# BatManagement.net
KiCad netlist of a schematic drawn in EAGLE
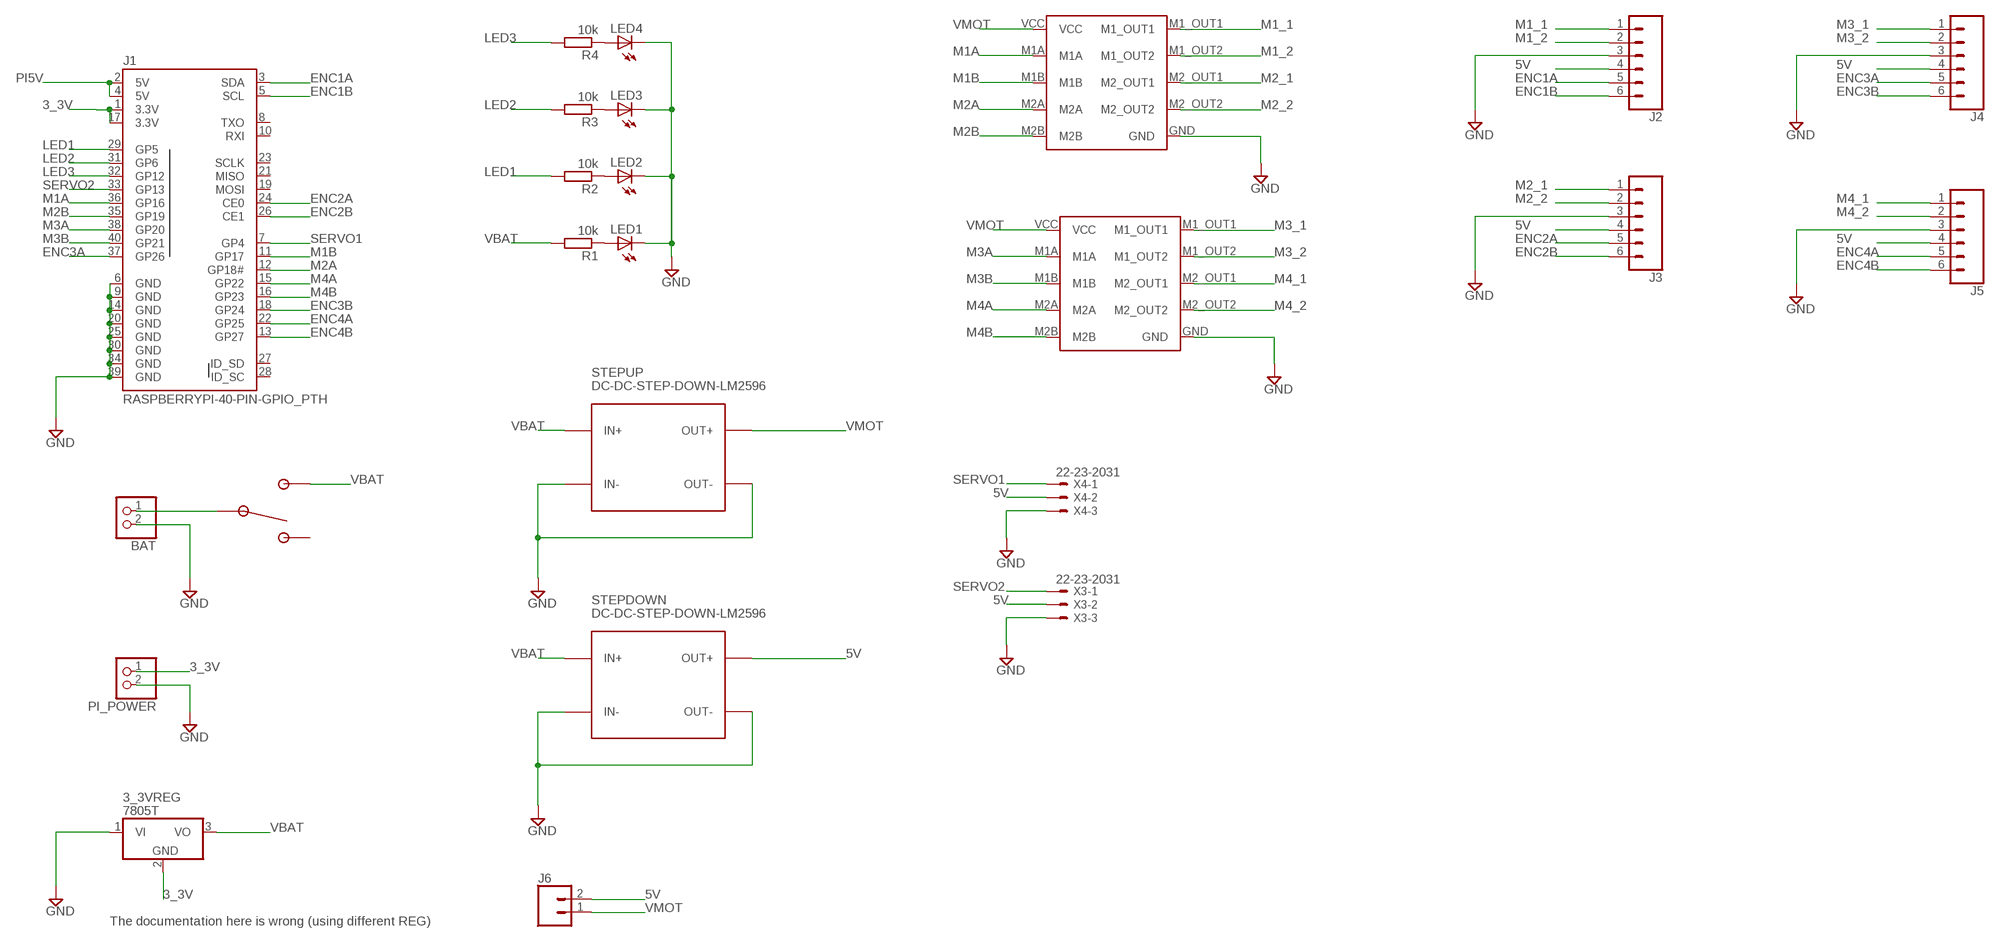
[diagram p0: schematic, sheet 1]

(export (version "E")
  (design (tool "Eeschema 10.0.6"))
  (components
    (comp (ref "3_3VREG")
      (value "7805T")
      (footprint "eagle-import:TO220H")
      (libsource (lib "eagle-import") (part "78T05"))
    )
    (comp (ref "BAT")
      (value "JST_2PIN-THM")
      (footprint "eagle-import:JST-PH-2-THM")
      (libsource (lib "eagle-import") (part "JST_2PIN-THM"))
    )
    (comp (ref "J1")
      (value "RASPBERRYPI-40-PIN-GPIO_PTH")
      (footprint "eagle-import:2X20_SHROUDED")
      (libsource (lib "eagle-import") (part "RASPBERRYPI-40-PIN-GPIO_PTH"))
    )
    (comp (ref "J2")
      (value "CONN_06SILK_FEMALE_PTH")
      (footprint "eagle-import:1X06")
      (libsource (lib "eagle-import") (part "CONN_06SILK_FEMALE_PTH"))
    )
    (comp (ref "J3")
      (value "CONN_06SILK_FEMALE_PTH")
      (footprint "eagle-import:1X06")
      (libsource (lib "eagle-import") (part "CONN_06SILK_FEMALE_PTH"))
    )
    (comp (ref "J4")
      (value "CONN_06SILK_FEMALE_PTH")
      (footprint "eagle-import:1X06")
      (libsource (lib "eagle-import") (part "CONN_06SILK_FEMALE_PTH"))
    )
    (comp (ref "J5")
      (value "CONN_06SILK_FEMALE_PTH")
      (footprint "eagle-import:1X06")
      (libsource (lib "eagle-import") (part "CONN_06SILK_FEMALE_PTH"))
    )
    (comp (ref "J6")
      (value "CONN_02")
      (footprint "eagle-import:1X02")
      (libsource (lib "eagle-import") (part "CONN_02"))
    )
    (comp (ref "LED1")
      (value "LED5MM")
      (footprint "eagle-import:LED5MM")
      (libsource (lib "eagle-import") (part "LED5MM"))
    )
    (comp (ref "LED2")
      (value "LED5MM")
      (footprint "eagle-import:LED5MM")
      (libsource (lib "eagle-import") (part "LED5MM"))
    )
    (comp (ref "LED3")
      (value "LED5MM")
      (footprint "eagle-import:LED5MM")
      (libsource (lib "eagle-import") (part "LED5MM"))
    )
    (comp (ref "LED4")
      (value "LED5MM")
      (footprint "eagle-import:LED5MM")
      (libsource (lib "eagle-import") (part "LED5MM"))
    )
    (comp (ref "MDRIVER1")
      (value "LV8548MC_BOARD")
      (footprint "eagle-import:LV8548MC_BOARD")
      (libsource (lib "eagle-import") (part "LV8548MC_BOARD"))
    )
    (comp (ref "MDRIVER2")
      (value "LV8548MC_BOARD")
      (footprint "eagle-import:LV8548MC_BOARD")
      (libsource (lib "eagle-import") (part "LV8548MC_BOARD"))
    )
    (comp (ref "PI_POWER")
      (value "JST_2PIN-THM")
      (footprint "eagle-import:JST-PH-2-THM")
      (libsource (lib "eagle-import") (part "JST_2PIN-THM"))
    )
    (comp (ref "R1")
      (value "10k")
      (footprint "eagle-import:0204_5")
      (libsource (lib "eagle-import") (part "R-EU_0204/5"))
    )
    (comp (ref "R2")
      (value "10k")
      (footprint "eagle-import:0204_5")
      (libsource (lib "eagle-import") (part "R-EU_0204/5"))
    )
    (comp (ref "R3")
      (value "10k")
      (footprint "eagle-import:0204_5")
      (libsource (lib "eagle-import") (part "R-EU_0204/5"))
    )
    (comp (ref "R4")
      (value "10k")
      (footprint "eagle-import:0204_5")
      (libsource (lib "eagle-import") (part "R-EU_0204/5"))
    )
    (comp (ref "STEPDOWN")
      (value "DC-DC-STEP-DOWN-LM2596")
      (footprint "eagle-import:DC-DC-STEP-DOWN-LM2596")
      (libsource (lib "eagle-import") (part "DC-DC-STEP-DOWN-LM2596"))
    )
    (comp (ref "STEPUP")
      (value "DC-DC-STEP-DOWN-LM2596")
      (footprint "eagle-import:DC-DC-STEP-DOWN-LM2596")
      (libsource (lib "eagle-import") (part "DC-DC-STEP-DOWN-LM2596"))
    )
    (comp (ref "SW1")
      (value "100SP1T2B4M6QE")
      (footprint "eagle-import:TOGGLE_RA")
      (fields (field (name "MF") "E-Switch"))
      (libsource (lib "eagle-import") (part "100SP1T2B4M6QE"))
    )
    (comp (ref "X3")
      (value "22-23-2031")
      (footprint "eagle-import:22-23-2031")
      (fields (field (name "MF") "MOLEX"))
      (libsource (lib "eagle-import") (part "22-23-2031"))
    )
    (comp (ref "X4")
      (value "22-23-2031")
      (footprint "eagle-import:22-23-2031")
      (fields (field (name "MF") "MOLEX"))
      (libsource (lib "eagle-import") (part "22-23-2031"))
    )
  )
  (nets
    (net (code "1") (name "/3_3V") (class "Default")
      (node (ref "3_3VREG") (pin "2") (pinfunction "GND_2") (pintype "passive"))
      (node (ref "J1") (pin "1") (pinfunction "3.3V_1") (pintype "power_in"))
      (node (ref "J1") (pin "17") (pinfunction "3.3V_17") (pintype "power_in"))
      (node (ref "PI_POWER") (pin "1") (pinfunction "2_1") (pintype "passive"))
    )
    (net (code "2") (name "/5V") (class "Default")
      (node (ref "J2") (pin "4") (pinfunction "4_4") (pintype "passive"))
      (node (ref "J3") (pin "4") (pinfunction "4_4") (pintype "passive"))
      (node (ref "J4") (pin "4") (pinfunction "4_4") (pintype "passive"))
      (node (ref "J5") (pin "4") (pinfunction "4_4") (pintype "passive"))
      (node (ref "J6") (pin "2") (pinfunction "2_2") (pintype "passive"))
      (node (ref "STEPDOWN") (pin "OUT+") (pinfunction "OUT+_OUT+") (pintype "bidirectional"))
      (node (ref "X3") (pin "2") (pinfunction "S_2") (pintype "passive"))
      (node (ref "X4") (pin "2") (pinfunction "S_2") (pintype "passive"))
    )
    (net (code "3") (name "/ENC1A") (class "Default")
      (node (ref "J1") (pin "3") (pinfunction "SDA_3") (pintype "bidirectional"))
      (node (ref "J2") (pin "5") (pinfunction "5_5") (pintype "passive"))
    )
    (net (code "4") (name "/ENC1B") (class "Default")
      (node (ref "J1") (pin "5") (pinfunction "SCL_5") (pintype "bidirectional"))
      (node (ref "J2") (pin "6") (pinfunction "6_6") (pintype "passive"))
    )
    (net (code "5") (name "/ENC2A") (class "Default")
      (node (ref "J1") (pin "24") (pinfunction "CE0_24") (pintype "output"))
      (node (ref "J3") (pin "5") (pinfunction "5_5") (pintype "passive"))
    )
    (net (code "6") (name "/ENC2B") (class "Default")
      (node (ref "J1") (pin "26") (pinfunction "CE1_26") (pintype "output"))
      (node (ref "J3") (pin "6") (pinfunction "6_6") (pintype "passive"))
    )
    (net (code "7") (name "/ENC3A") (class "Default")
      (node (ref "J1") (pin "37") (pinfunction "GP26_37") (pintype "bidirectional"))
      (node (ref "J4") (pin "5") (pinfunction "5_5") (pintype "passive"))
    )
    (net (code "8") (name "/ENC3B") (class "Default")
      (node (ref "J1") (pin "18") (pinfunction "GP24_18") (pintype "bidirectional"))
      (node (ref "J4") (pin "6") (pinfunction "6_6") (pintype "passive"))
    )
    (net (code "9") (name "/ENC4A") (class "Default")
      (node (ref "J1") (pin "22") (pinfunction "GP25_22") (pintype "bidirectional"))
      (node (ref "J5") (pin "5") (pinfunction "5_5") (pintype "passive"))
    )
    (net (code "10") (name "/ENC4B") (class "Default")
      (node (ref "J1") (pin "13") (pinfunction "GP27_13") (pintype "bidirectional"))
      (node (ref "J5") (pin "6") (pinfunction "6_6") (pintype "passive"))
    )
    (net (code "11") (name "/LED1") (class "Default")
      (node (ref "J1") (pin "29") (pinfunction "GP5_29") (pintype "bidirectional"))
      (node (ref "R2") (pin "2") (pinfunction "2_2") (pintype "passive"))
    )
    (net (code "12") (name "/LED2") (class "Default")
      (node (ref "J1") (pin "31") (pinfunction "GP6_31") (pintype "bidirectional"))
      (node (ref "R3") (pin "2") (pinfunction "2_2") (pintype "passive"))
    )
    (net (code "13") (name "/LED3") (class "Default")
      (node (ref "J1") (pin "32") (pinfunction "GP12_32") (pintype "bidirectional"))
      (node (ref "R4") (pin "2") (pinfunction "2_2") (pintype "passive"))
    )
    (net (code "14") (name "/M1A") (class "Default")
      (node (ref "J1") (pin "36") (pinfunction "GP16_36") (pintype "bidirectional"))
      (node (ref "MDRIVER1") (pin "M1A") (pinfunction "M1A_M1A") (pintype "bidirectional"))
    )
    (net (code "15") (name "/M1B") (class "Default")
      (node (ref "J1") (pin "11") (pinfunction "GP17_11") (pintype "bidirectional"))
      (node (ref "MDRIVER1") (pin "M1B") (pinfunction "M1B_M1B") (pintype "bidirectional"))
    )
    (net (code "16") (name "/M1_1") (class "Default")
      (node (ref "J2") (pin "1") (pinfunction "1_1") (pintype "passive"))
      (node (ref "MDRIVER1") (pin "M1_OUT1") (pinfunction "M1_OUT1_M1_OUT1") (pintype "bidirectional"))
    )
    (net (code "17") (name "/M1_2") (class "Default")
      (node (ref "J2") (pin "2") (pinfunction "2_2") (pintype "passive"))
      (node (ref "MDRIVER1") (pin "M1_OUT2") (pinfunction "M1_OUT2_M1_OUT2") (pintype "bidirectional"))
    )
    (net (code "18") (name "/M2A") (class "Default")
      (node (ref "J1") (pin "12") (pinfunction "GP18#_12") (pintype "bidirectional"))
      (node (ref "MDRIVER1") (pin "M2A") (pinfunction "M2A_M2A") (pintype "bidirectional"))
    )
    (net (code "19") (name "/M2B") (class "Default")
      (node (ref "J1") (pin "35") (pinfunction "GP19_35") (pintype "bidirectional"))
      (node (ref "MDRIVER1") (pin "M2B") (pinfunction "M2B_M2B") (pintype "bidirectional"))
    )
    (net (code "20") (name "/M2_1") (class "Default")
      (node (ref "J3") (pin "1") (pinfunction "1_1") (pintype "passive"))
      (node (ref "MDRIVER1") (pin "M2_OUT1") (pinfunction "M2_OUT1_M2_OUT1") (pintype "bidirectional"))
    )
    (net (code "21") (name "/M2_2") (class "Default")
      (node (ref "J3") (pin "2") (pinfunction "2_2") (pintype "passive"))
      (node (ref "MDRIVER1") (pin "M2_OUT2") (pinfunction "M2_OUT2_M2_OUT2") (pintype "bidirectional"))
    )
    (net (code "22") (name "/M3A") (class "Default")
      (node (ref "J1") (pin "38") (pinfunction "GP20_38") (pintype "bidirectional"))
      (node (ref "MDRIVER2") (pin "M1A") (pinfunction "M1A_M1A") (pintype "bidirectional"))
    )
    (net (code "23") (name "/M3B") (class "Default")
      (node (ref "J1") (pin "40") (pinfunction "GP21_40") (pintype "bidirectional"))
      (node (ref "MDRIVER2") (pin "M1B") (pinfunction "M1B_M1B") (pintype "bidirectional"))
    )
    (net (code "24") (name "/M3_1") (class "Default")
      (node (ref "J4") (pin "1") (pinfunction "1_1") (pintype "passive"))
      (node (ref "MDRIVER2") (pin "M1_OUT1") (pinfunction "M1_OUT1_M1_OUT1") (pintype "bidirectional"))
    )
    (net (code "25") (name "/M3_2") (class "Default")
      (node (ref "J4") (pin "2") (pinfunction "2_2") (pintype "passive"))
      (node (ref "MDRIVER2") (pin "M1_OUT2") (pinfunction "M1_OUT2_M1_OUT2") (pintype "bidirectional"))
    )
    (net (code "26") (name "/M4A") (class "Default")
      (node (ref "J1") (pin "15") (pinfunction "GP22_15") (pintype "bidirectional"))
      (node (ref "MDRIVER2") (pin "M2A") (pinfunction "M2A_M2A") (pintype "bidirectional"))
    )
    (net (code "27") (name "/M4B") (class "Default")
      (node (ref "J1") (pin "16") (pinfunction "GP23_16") (pintype "bidirectional"))
      (node (ref "MDRIVER2") (pin "M2B") (pinfunction "M2B_M2B") (pintype "bidirectional"))
    )
    (net (code "28") (name "/M4_1") (class "Default")
      (node (ref "J5") (pin "1") (pinfunction "1_1") (pintype "passive"))
      (node (ref "MDRIVER2") (pin "M2_OUT1") (pinfunction "M2_OUT1_M2_OUT1") (pintype "bidirectional"))
    )
    (net (code "29") (name "/M4_2") (class "Default")
      (node (ref "J5") (pin "2") (pinfunction "2_2") (pintype "passive"))
      (node (ref "MDRIVER2") (pin "M2_OUT2") (pinfunction "M2_OUT2_M2_OUT2") (pintype "bidirectional"))
    )
    (net (code "30") (name "/PI5V") (class "Default")
      (node (ref "J1") (pin "2") (pinfunction "5V_2") (pintype "power_in"))
      (node (ref "J1") (pin "4") (pinfunction "5V_4") (pintype "power_in"))
    )
    (net (code "31") (name "/SERVO1") (class "Default")
      (node (ref "J1") (pin "7") (pinfunction "GP4_7") (pintype "bidirectional"))
      (node (ref "X4") (pin "1") (pinfunction "S_1") (pintype "passive"))
    )
    (net (code "32") (name "/SERVO2") (class "Default")
      (node (ref "J1") (pin "33") (pinfunction "GP13_33") (pintype "bidirectional"))
      (node (ref "X3") (pin "1") (pinfunction "S_1") (pintype "passive"))
    )
    (net (code "33") (name "/VBAT") (class "Default")
      (node (ref "3_3VREG") (pin "3") (pinfunction "VO_3") (pintype "passive"))
      (node (ref "R1") (pin "2") (pinfunction "2_2") (pintype "passive"))
      (node (ref "STEPDOWN") (pin "IN+") (pinfunction "IN+_IN+") (pintype "bidirectional"))
      (node (ref "STEPUP") (pin "IN+") (pinfunction "IN+_IN+") (pintype "bidirectional"))
      (node (ref "SW1") (pin "1") (pinfunction "P$2_1") (pintype "bidirectional"))
    )
    (net (code "34") (name "/VMOT") (class "Default")
      (node (ref "J6") (pin "1") (pinfunction "1_1") (pintype "passive"))
      (node (ref "MDRIVER1") (pin "VCC") (pinfunction "VCC_VCC") (pintype "bidirectional"))
      (node (ref "MDRIVER2") (pin "VCC") (pinfunction "VCC_VCC") (pintype "bidirectional"))
      (node (ref "STEPUP") (pin "OUT+") (pinfunction "OUT+_OUT+") (pintype "bidirectional"))
    )
    (net (code "35") (name "GND") (class "Default")
      (node (ref "3_3VREG") (pin "1") (pinfunction "VI_1") (pintype "input"))
      (node (ref "BAT") (pin "2") (pinfunction "1_2") (pintype "passive"))
      (node (ref "J1") (pin "14") (pinfunction "GND_14") (pintype "power_in"))
      (node (ref "J1") (pin "20") (pinfunction "GND_20") (pintype "power_in"))
      (node (ref "J1") (pin "25") (pinfunction "GND_25") (pintype "power_in"))
      (node (ref "J1") (pin "30") (pinfunction "GND_30") (pintype "power_in"))
      (node (ref "J1") (pin "34") (pinfunction "GND_34") (pintype "power_in"))
      (node (ref "J1") (pin "39") (pinfunction "GND_39") (pintype "power_in"))
      (node (ref "J1") (pin "6") (pinfunction "GND_6") (pintype "power_in"))
      (node (ref "J1") (pin "9") (pinfunction "GND_9") (pintype "power_in"))
      (node (ref "J2") (pin "3") (pinfunction "3_3") (pintype "passive"))
      (node (ref "J3") (pin "3") (pinfunction "3_3") (pintype "passive"))
      (node (ref "J4") (pin "3") (pinfunction "3_3") (pintype "passive"))
      (node (ref "J5") (pin "3") (pinfunction "3_3") (pintype "passive"))
      (node (ref "LED1") (pin "K") (pinfunction "C_K") (pintype "passive"))
      (node (ref "LED2") (pin "K") (pinfunction "C_K") (pintype "passive"))
      (node (ref "LED3") (pin "K") (pinfunction "C_K") (pintype "passive"))
      (node (ref "LED4") (pin "K") (pinfunction "C_K") (pintype "passive"))
      (node (ref "MDRIVER1") (pin "GND") (pinfunction "GND_GND") (pintype "bidirectional"))
      (node (ref "MDRIVER2") (pin "GND") (pinfunction "GND_GND") (pintype "bidirectional"))
      (node (ref "PI_POWER") (pin "2") (pinfunction "1_2") (pintype "passive"))
      (node (ref "STEPDOWN") (pin "IN-") (pinfunction "IN-_IN-") (pintype "bidirectional"))
      (node (ref "STEPDOWN") (pin "OUT-") (pinfunction "OUT-_OUT-") (pintype "bidirectional"))
      (node (ref "STEPUP") (pin "IN-") (pinfunction "IN-_IN-") (pintype "bidirectional"))
      (node (ref "STEPUP") (pin "OUT-") (pinfunction "OUT-_OUT-") (pintype "bidirectional"))
      (node (ref "X3") (pin "3") (pinfunction "S_3") (pintype "passive"))
      (node (ref "X4") (pin "3") (pinfunction "S_3") (pintype "passive"))
    )
    (net (code "36") (name "Net-(BAT-2)") (class "Default")
      (node (ref "BAT") (pin "1") (pinfunction "2_1") (pintype "passive"))
      (node (ref "SW1") (pin "2") (pinfunction "COM_2") (pintype "bidirectional"))
    )
    (net (code "37") (name "Net-(LED1-PadA)") (class "Default")
      (node (ref "LED1") (pin "A") (pinfunction "A_A") (pintype "passive"))
      (node (ref "R1") (pin "1") (pinfunction "1_1") (pintype "passive"))
    )
    (net (code "38") (name "Net-(LED2-PadA)") (class "Default")
      (node (ref "LED2") (pin "A") (pinfunction "A_A") (pintype "passive"))
      (node (ref "R2") (pin "1") (pinfunction "1_1") (pintype "passive"))
    )
    (net (code "39") (name "Net-(LED3-PadA)") (class "Default")
      (node (ref "LED3") (pin "A") (pinfunction "A_A") (pintype "passive"))
      (node (ref "R3") (pin "1") (pinfunction "1_1") (pintype "passive"))
    )
    (net (code "40") (name "Net-(LED4-PadA)") (class "Default")
      (node (ref "LED4") (pin "A") (pinfunction "A_A") (pintype "passive"))
      (node (ref "R4") (pin "1") (pinfunction "1_1") (pintype "passive"))
    )
    (net (code "41") (name "unconnected-(J1-ID_SC-Pad28)") (class "Default")
      (node (ref "J1") (pin "28") (pinfunction "ID_SC_28") (pintype "bidirectional"))
    )
    (net (code "42") (name "unconnected-(J1-ID_SD-Pad27)") (class "Default")
      (node (ref "J1") (pin "27") (pinfunction "ID_SD_27") (pintype "bidirectional"))
    )
    (net (code "43") (name "unconnected-(J1-MISO-Pad21)") (class "Default")
      (node (ref "J1") (pin "21") (pinfunction "MISO_21") (pintype "input"))
    )
    (net (code "44") (name "unconnected-(J1-MOSI-Pad19)") (class "Default")
      (node (ref "J1") (pin "19") (pinfunction "MOSI_19") (pintype "output"))
    )
    (net (code "45") (name "unconnected-(J1-RXI-Pad10)") (class "Default")
      (node (ref "J1") (pin "10") (pinfunction "RXI_10") (pintype "input"))
    )
    (net (code "46") (name "unconnected-(J1-SCLK-Pad23)") (class "Default")
      (node (ref "J1") (pin "23") (pinfunction "SCLK_23") (pintype "output"))
    )
    (net (code "47") (name "unconnected-(J1-TXO-Pad8)") (class "Default")
      (node (ref "J1") (pin "8") (pinfunction "TXO_8") (pintype "output"))
    )
    (net (code "48") (name "unconnected-(SW1-P$3-Pad3)") (class "Default")
      (node (ref "SW1") (pin "3") (pinfunction "P$3_3") (pintype "bidirectional"))
    )
  )
)
